# KAKUTE_mini.net
KiCad netlist of a schematic drawn in EasyEDA Pro
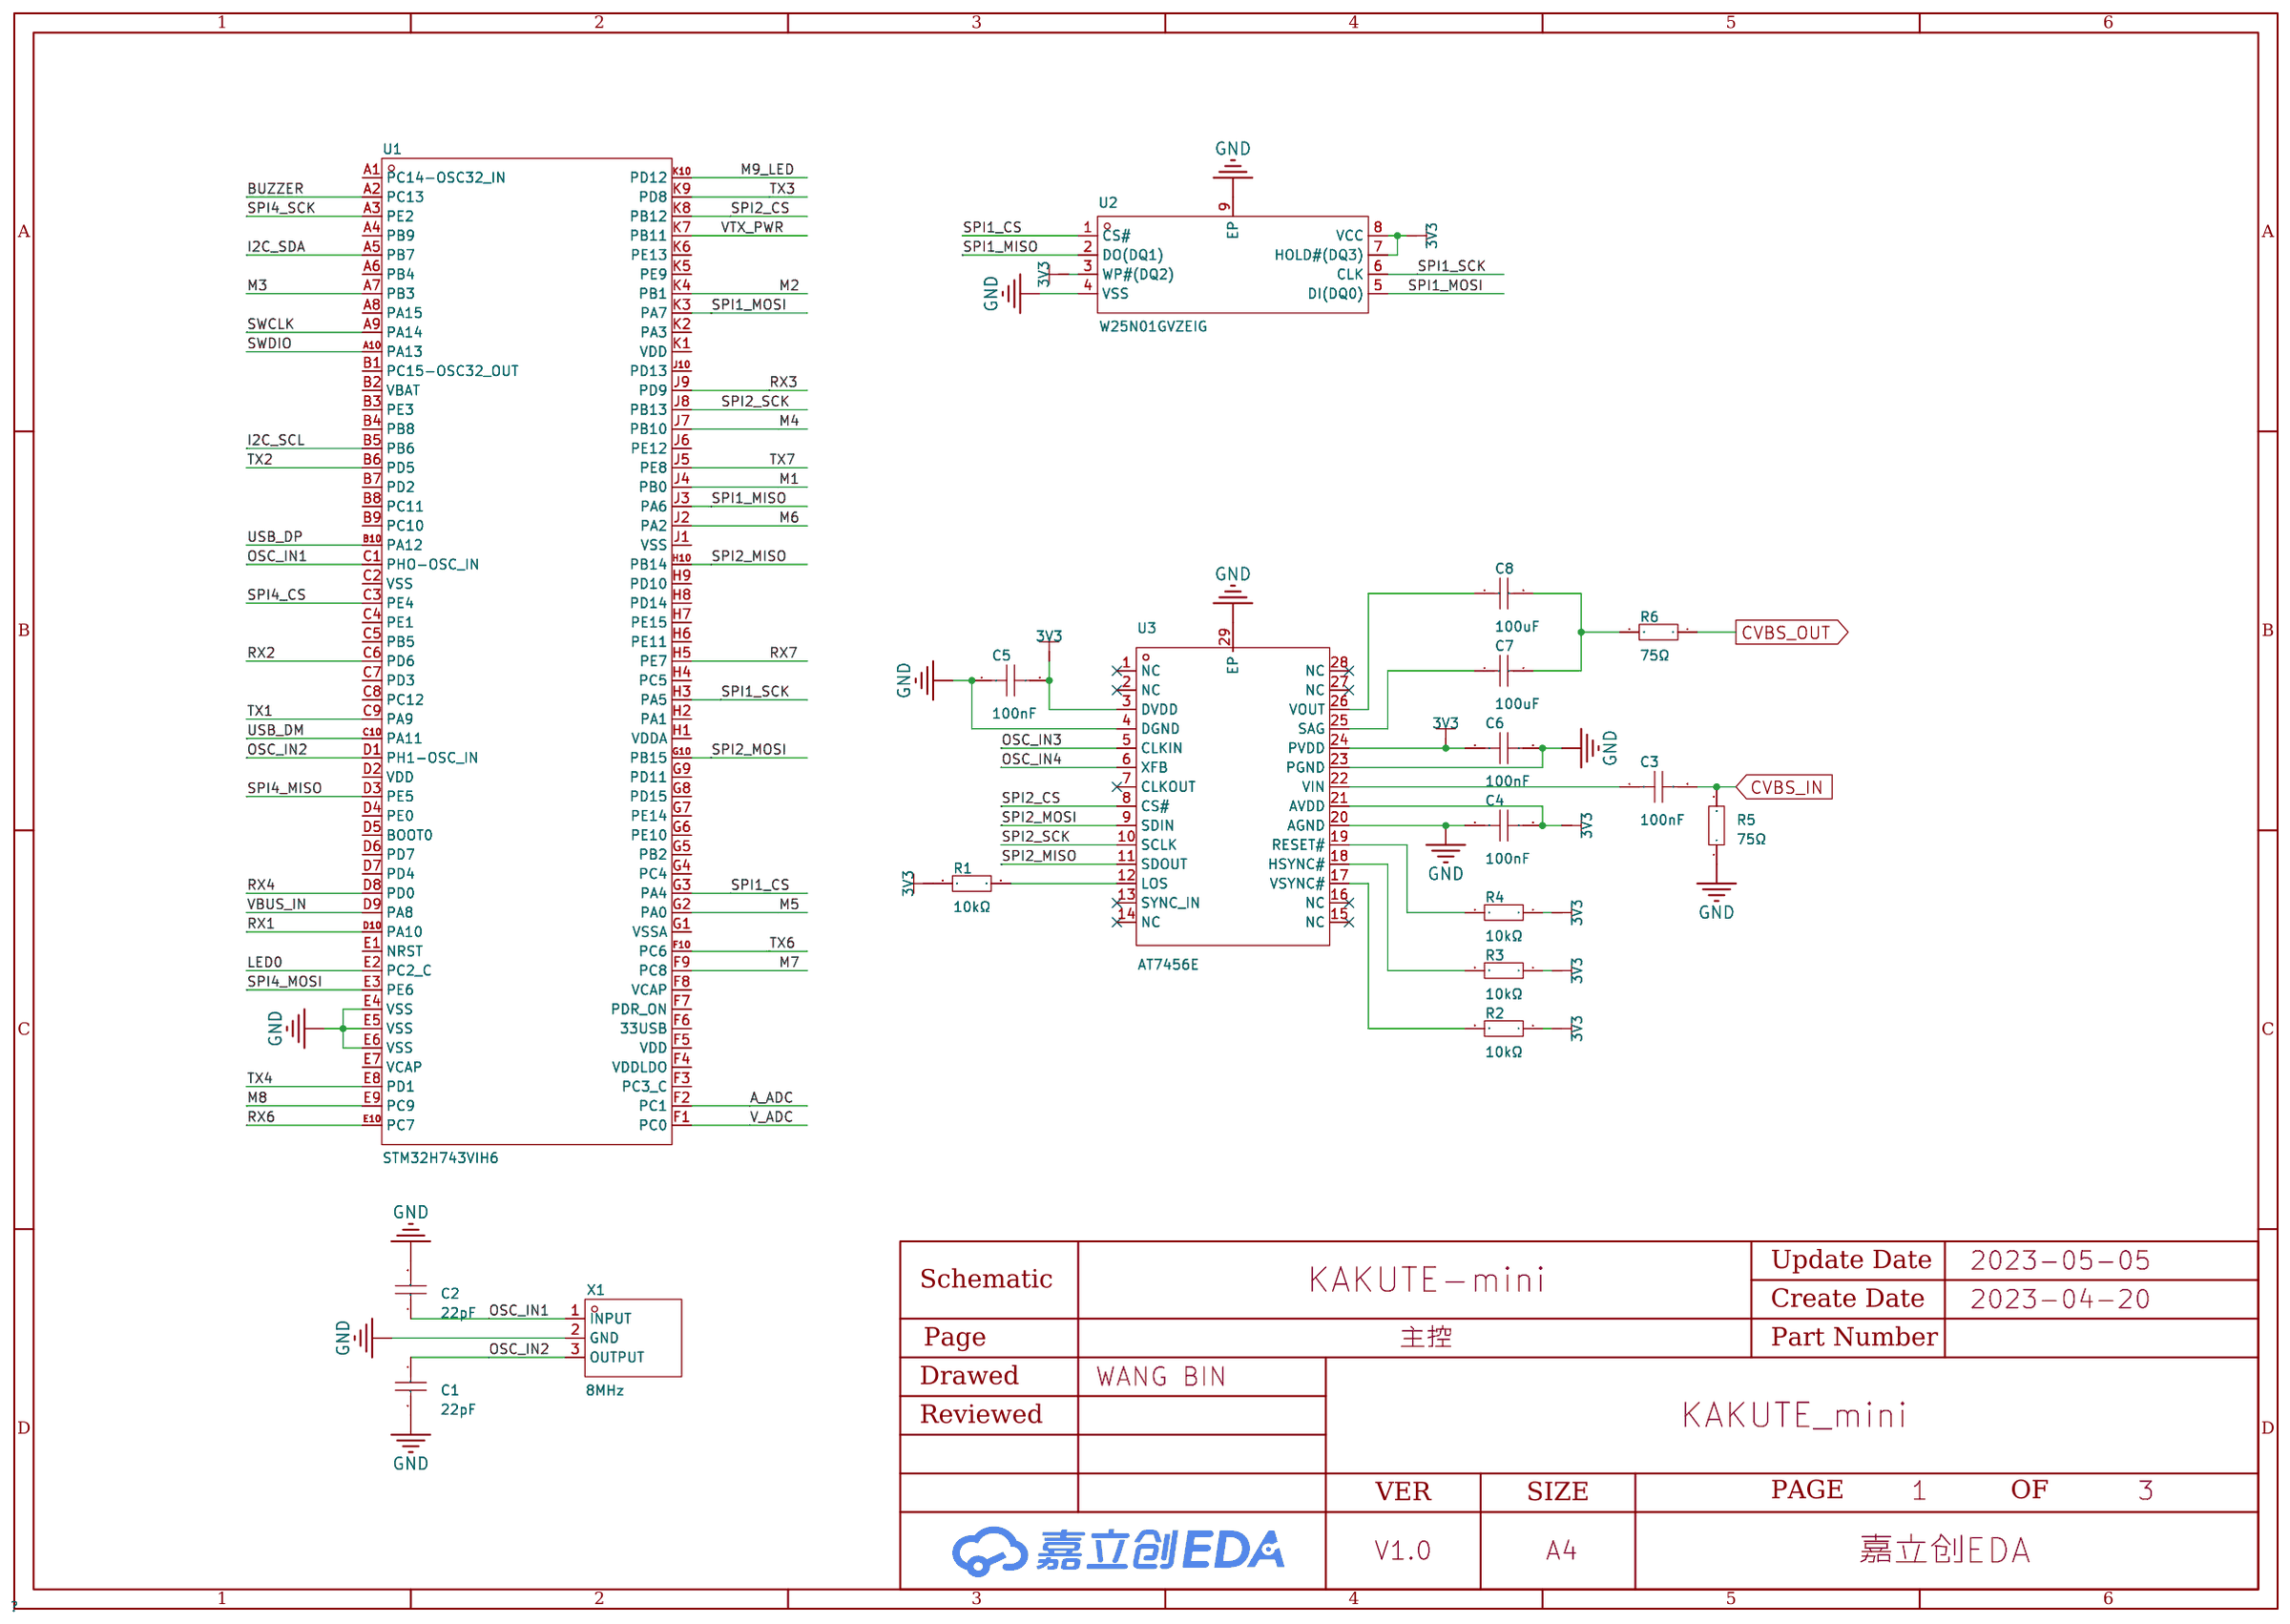
[diagram p0: 主控]
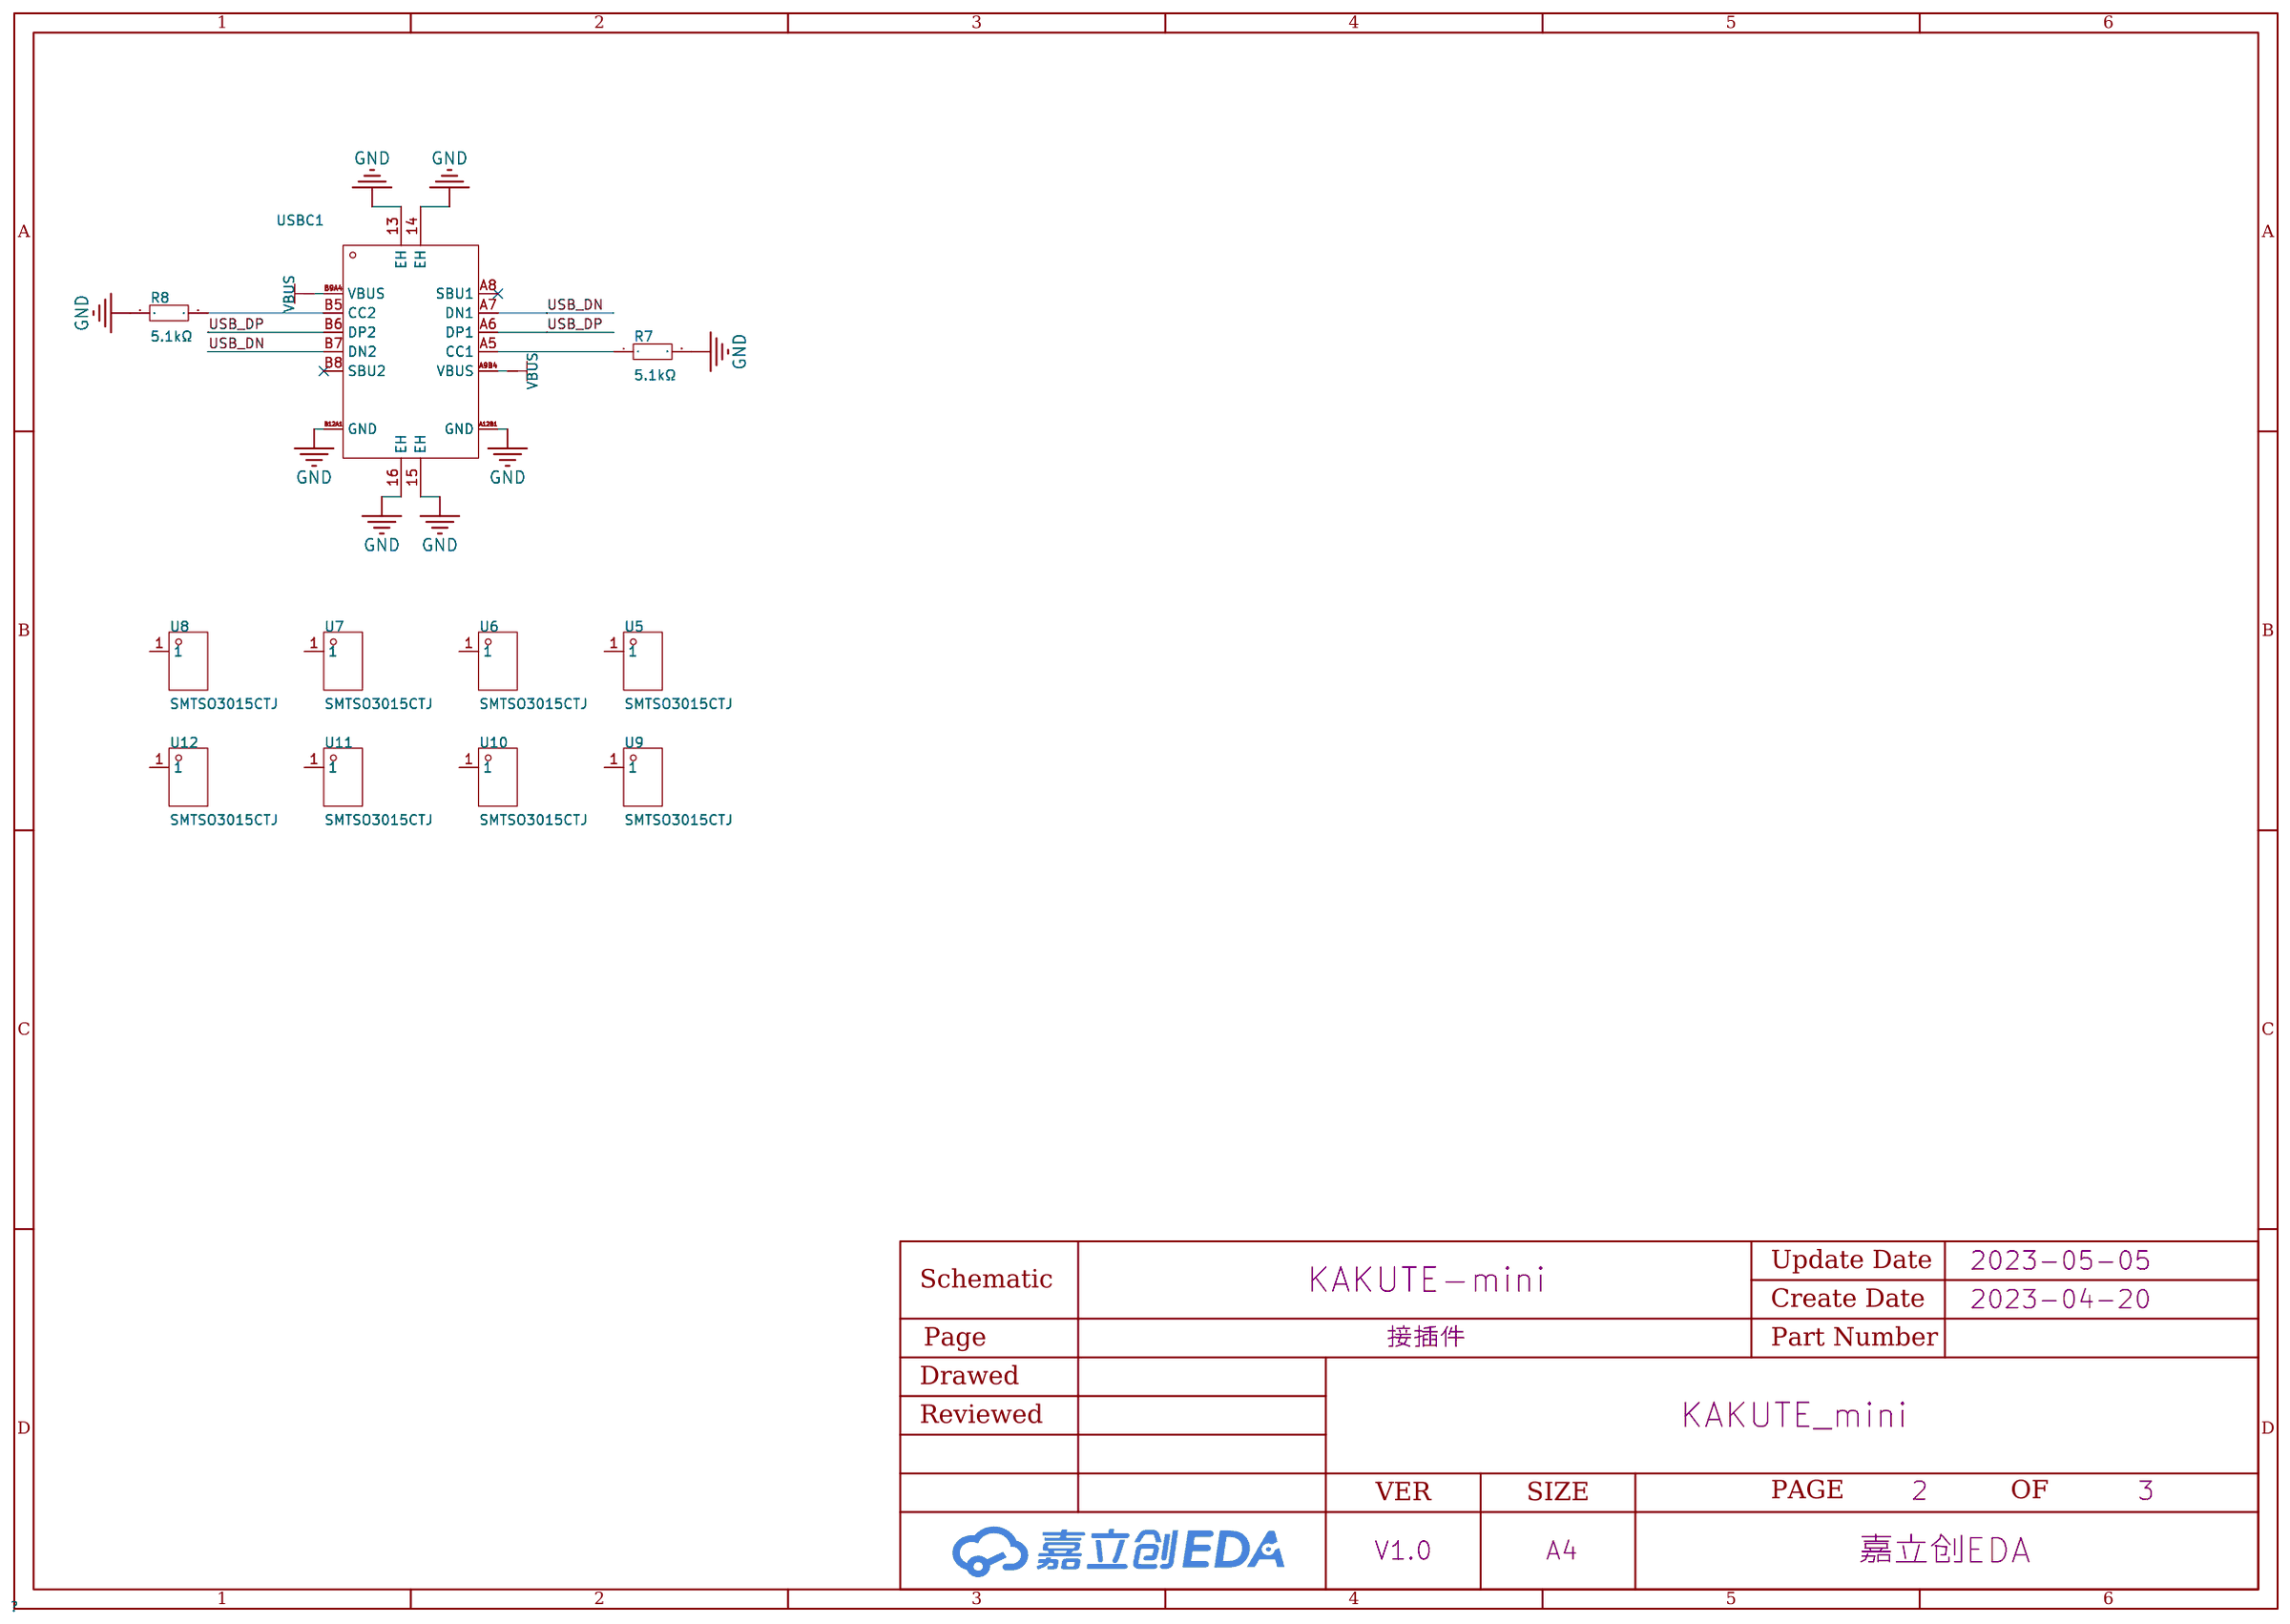
[diagram p1: 接插件]
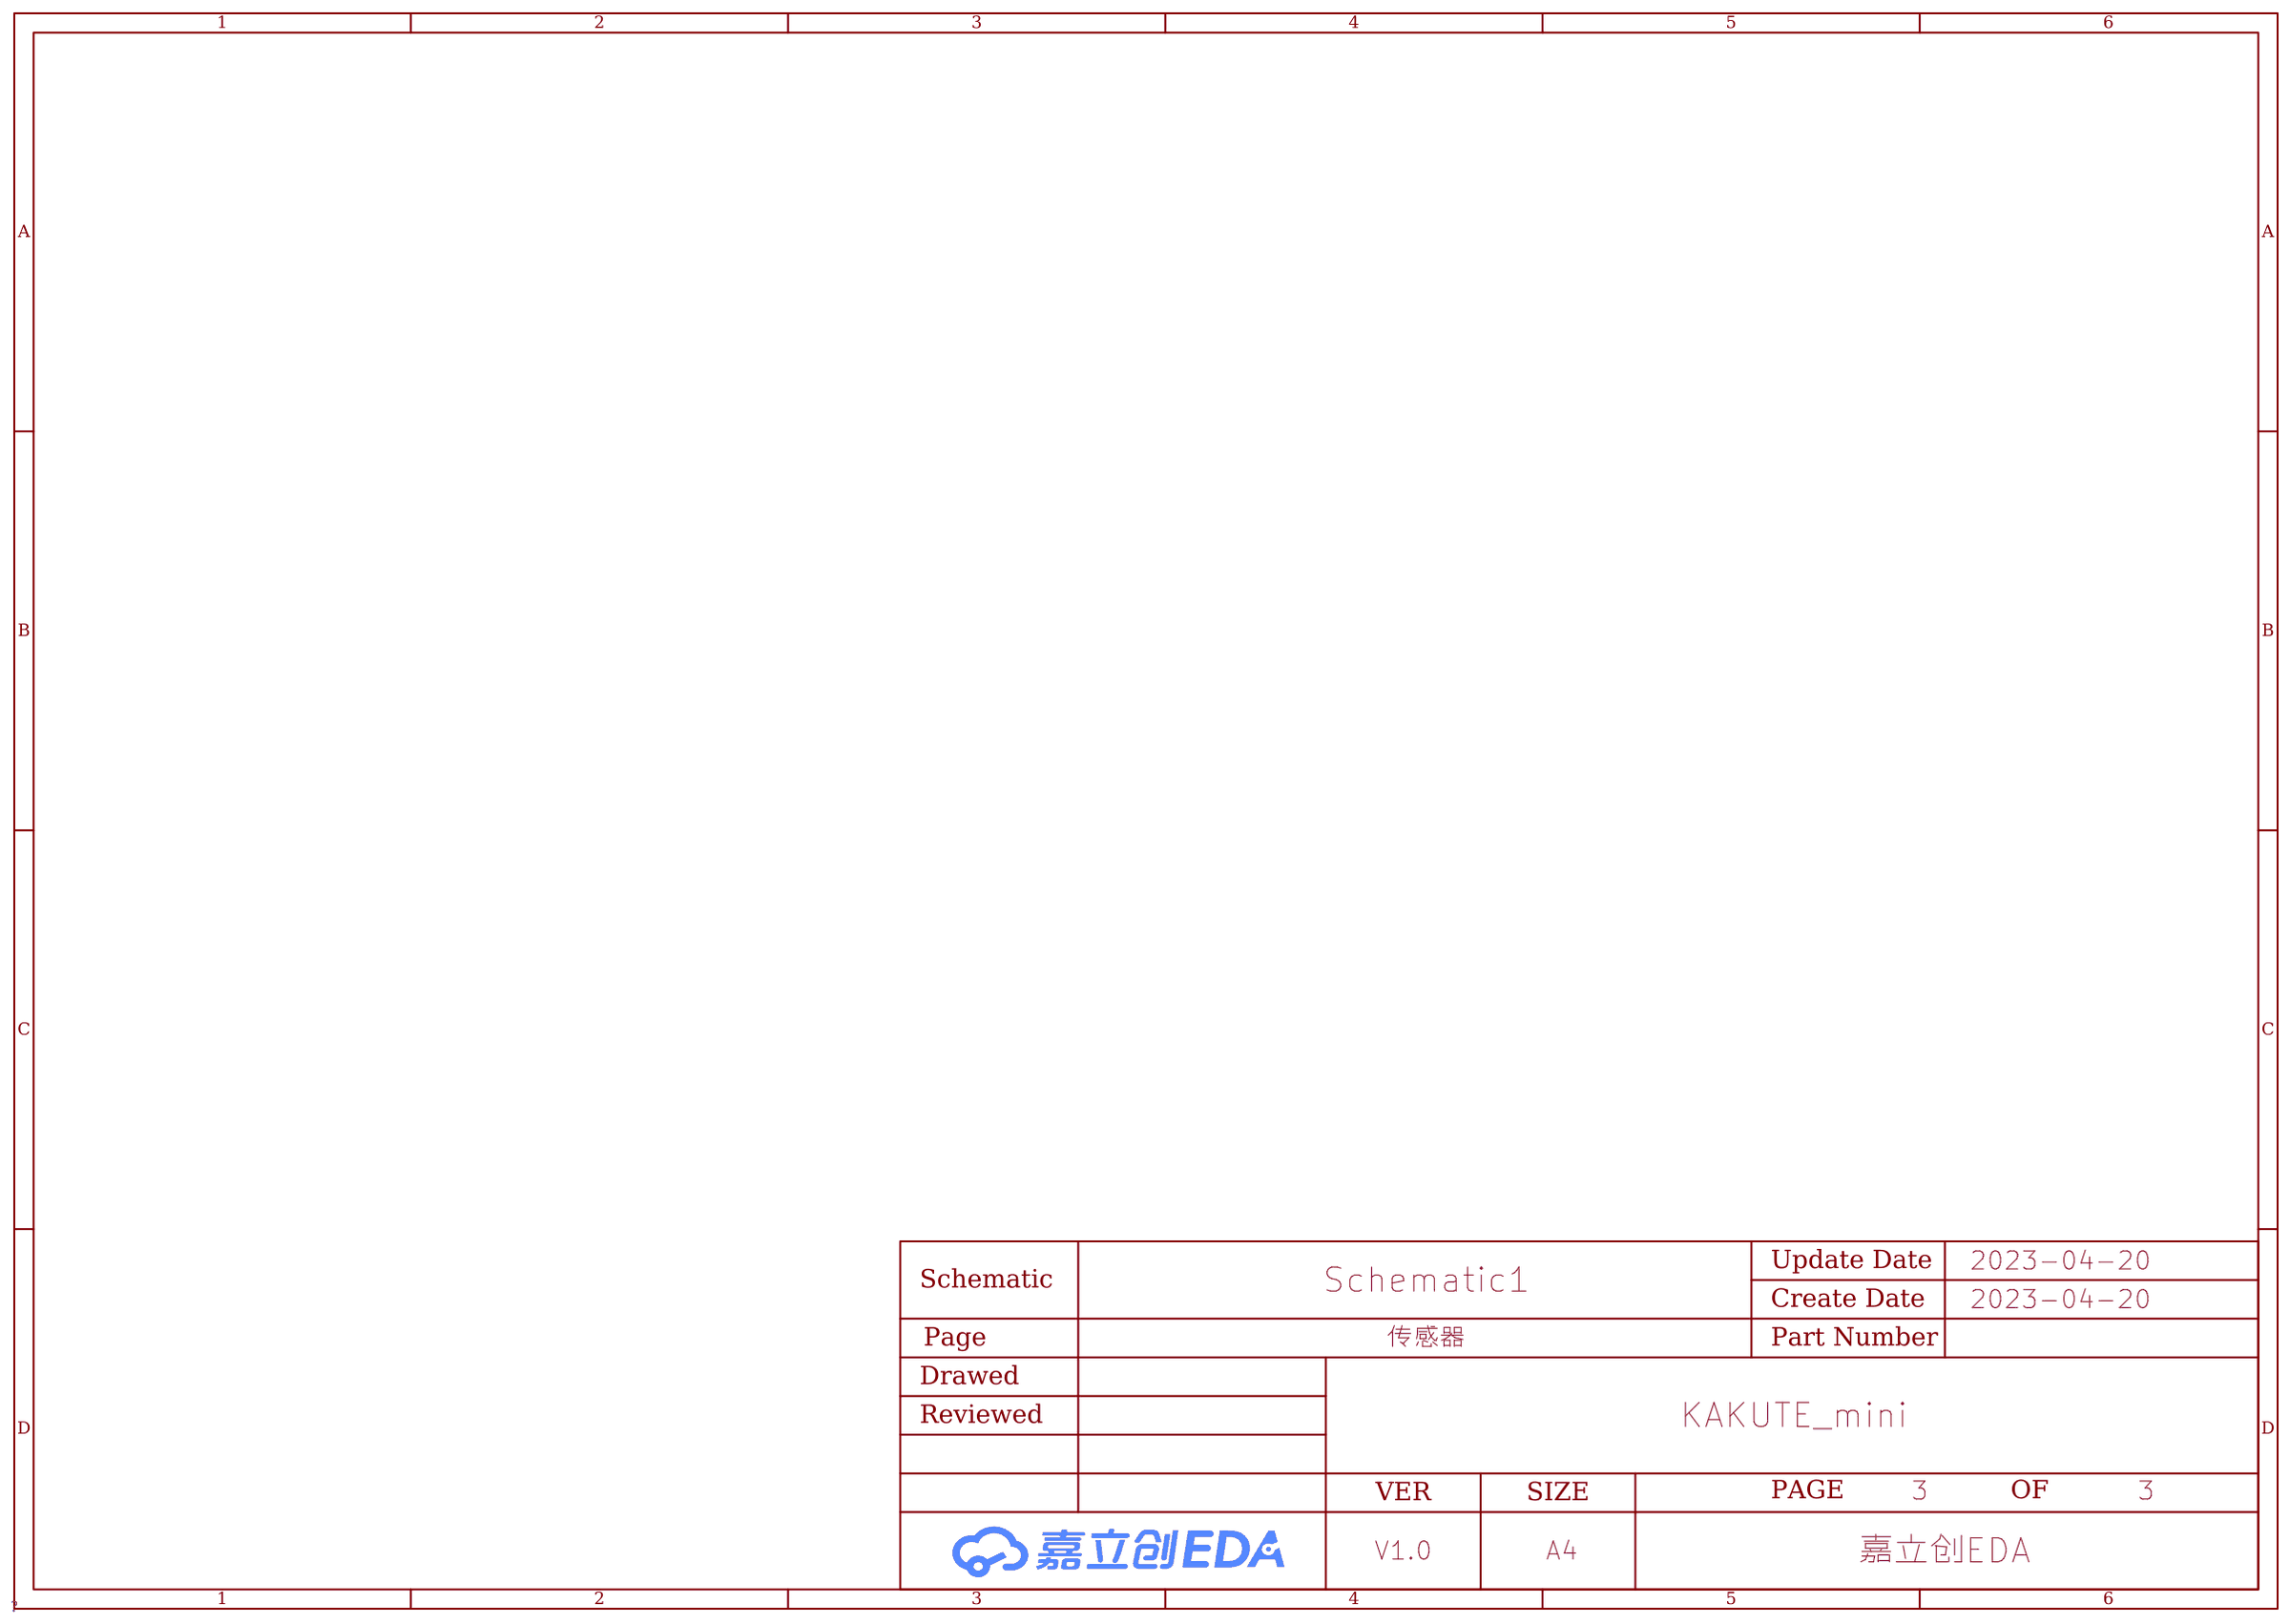
[diagram p2: 传感器]

(export (version "E")
  (design (tool "Eeschema 10.0.6"))
  (components
    (comp (ref "C1")
      (value "22pF")
      (footprint "easyedapro:C0402")
      (description "容值:22pF;精度:±5%;额定电压:50V;材质(温度系数):C0G;")
      (fields (field (name "Manufacturer Part") "0402CG220J500NT") (field (name "Manufacturer") "FH(风华)"))
      (libsource (lib "easyedapro") (part "0402CG220J500NT"))
    )
    (comp (ref "C2")
      (value "22pF")
      (footprint "easyedapro:C0402")
      (description "容值:22pF;精度:±5%;额定电压:50V;材质(温度系数):C0G;")
      (fields (field (name "Manufacturer Part") "0402CG220J500NT") (field (name "Manufacturer") "FH(风华)"))
      (libsource (lib "easyedapro") (part "0402CG220J500NT"))
    )
    (comp (ref "C3")
      (value "100nF")
      (footprint "easyedapro:C0402")
      (description "容值:100nF;精度:±10%;额定电压:50V;材质(温度系数):X7R;")
      (fields
        (field (name "Manufacturer Part") "CL05B104KB54PNC")
        (field (name "Manufacturer") "SAMSUNG(三星)")
      )
      (libsource (lib "easyedapro") (part "CL05B104KB54PNC"))
    )
    (comp (ref "C4")
      (value "100nF")
      (footprint "easyedapro:C0402")
      (description "容值:100nF;精度:±10%;额定电压:50V;材质(温度系数):X7R;")
      (fields
        (field (name "Manufacturer Part") "CL05B104KB54PNC")
        (field (name "Manufacturer") "SAMSUNG(三星)")
      )
      (libsource (lib "easyedapro") (part "CL05B104KB54PNC"))
    )
    (comp (ref "C5")
      (value "100nF")
      (footprint "easyedapro:C0402")
      (description "容值:100nF;精度:±10%;额定电压:50V;材质(温度系数):X7R;")
      (fields
        (field (name "Manufacturer Part") "CL05B104KB54PNC")
        (field (name "Manufacturer") "SAMSUNG(三星)")
      )
      (libsource (lib "easyedapro") (part "CL05B104KB54PNC"))
    )
    (comp (ref "C6")
      (value "100nF")
      (footprint "easyedapro:C0402")
      (description "容值:100nF;精度:±10%;额定电压:50V;材质(温度系数):X7R;")
      (fields
        (field (name "Manufacturer Part") "CL05B104KB54PNC")
        (field (name "Manufacturer") "SAMSUNG(三星)")
      )
      (libsource (lib "easyedapro") (part "CL05B104KB54PNC"))
    )
    (comp (ref "C7")
      (value "100uF")
      (footprint "easyedapro:C0805")
      (description "容值:100uF;精度:±20%;额定电压:6.3V;材质(温度系数):X5R;")
      (fields
        (field (name "Manufacturer Part") "GRM21BR60J107ME15L")
        (field (name "Manufacturer") "muRata(村田)")
      )
      (libsource (lib "easyedapro") (part "GRM21BR60J107ME15L"))
    )
    (comp (ref "C8")
      (value "100uF")
      (footprint "easyedapro:C0805")
      (description "容值:100uF;精度:±20%;额定电压:6.3V;材质(温度系数):X5R;")
      (fields
        (field (name "Manufacturer Part") "GRM21BR60J107ME15L")
        (field (name "Manufacturer") "muRata(村田)")
      )
      (libsource (lib "easyedapro") (part "GRM21BR60J107ME15L"))
    )
    (comp (ref "R1")
      (value "10kΩ")
      (footprint "easyedapro:R0402")
      (description "电阻类型:厚膜电阻;阻值:10kΩ;精度:±1%;功率:62.5mW;")
      (fields
        (field (name "Manufacturer Part") "0402WGF1002TCE")
        (field (name "Manufacturer") "UNI-ROYAL(厚声)")
      )
      (libsource (lib "easyedapro") (part "0402WGF1002TCE"))
    )
    (comp (ref "R2")
      (value "10kΩ")
      (footprint "easyedapro:R0402")
      (description "电阻类型:厚膜电阻;阻值:10kΩ;精度:±1%;功率:62.5mW;")
      (fields
        (field (name "Manufacturer Part") "0402WGF1002TCE")
        (field (name "Manufacturer") "UNI-ROYAL(厚声)")
      )
      (libsource (lib "easyedapro") (part "0402WGF1002TCE"))
    )
    (comp (ref "R3")
      (value "10kΩ")
      (footprint "easyedapro:R0402")
      (description "电阻类型:厚膜电阻;阻值:10kΩ;精度:±1%;功率:62.5mW;")
      (fields
        (field (name "Manufacturer Part") "0402WGF1002TCE")
        (field (name "Manufacturer") "UNI-ROYAL(厚声)")
      )
      (libsource (lib "easyedapro") (part "0402WGF1002TCE"))
    )
    (comp (ref "R4")
      (value "10kΩ")
      (footprint "easyedapro:R0402")
      (description "电阻类型:厚膜电阻;阻值:10kΩ;精度:±1%;功率:62.5mW;")
      (fields
        (field (name "Manufacturer Part") "0402WGF1002TCE")
        (field (name "Manufacturer") "UNI-ROYAL(厚声)")
      )
      (libsource (lib "easyedapro") (part "0402WGF1002TCE"))
    )
    (comp (ref "R5")
      (value "75Ω")
      (footprint "easyedapro:R0402")
      (description "电阻类型:厚膜电阻;阻值:75Ω;精度:±1%;功率:62.5mW;")
      (fields
        (field (name "Manufacturer Part") "0402WGF750JTCE")
        (field (name "Manufacturer") "UNI-ROYAL(厚声)")
      )
      (libsource (lib "easyedapro") (part "0402WGF750JTCE"))
    )
    (comp (ref "R6")
      (value "75Ω")
      (footprint "easyedapro:R0402")
      (description "电阻类型:厚膜电阻;阻值:75Ω;精度:±1%;功率:62.5mW;")
      (fields
        (field (name "Manufacturer Part") "0402WGF750JTCE")
        (field (name "Manufacturer") "UNI-ROYAL(厚声)")
      )
      (libsource (lib "easyedapro") (part "0402WGF750JTCE"))
    )
    (comp (ref "U1")
      (value "STM32H743VIH6")
      (footprint "easyedapro:BGA-100_L8.0-W8.0-P0.80-R10-C10-BL")
      (description "32位Arm Cortex -M7 480MHz mcu,高达2MB的Flash,高达1MB的RAM,46com和模拟接口")
      (fields (field (name "Manufacturer") "ST(意法半导体)"))
      (libsource (lib "easyedapro") (part "STM32H743VIH6"))
    )
    (comp (ref "U2")
      (value "W25N01GVZEIG")
      (footprint "easyedapro:WSON-8_L8.0-W6.10-P1.27-BL-EP")
      (description "存储器类型:-;存储器构架(格式):-;技术:-;存储器容量:-;时钟频率:-;存储器接口类型:-;")
      (fields (field (name "Manufacturer") "WINBOND(华邦)"))
      (libsource (lib "easyedapro") (part "W25N01GVZEIG_C907680"))
    )
    (comp (ref "U3")
      (value "AT7456E")
      (footprint "easyedapro:TSSOP-28_L9.7-W4.4-P0.65-LS6.4-BL-EP-2")
      (description "视频字符叠加芯片，跟MAX7456-pin-pin")
      (fields (field (name "Manufacturer") "杭州中科微"))
      (libsource (lib "easyedapro") (part "AT7456E"))
    )
    (comp (ref "X1")
      (value "8MHz")
      (footprint "easyedapro:OSC-SMD_3P-L3.2-W1.3-P1.20-L")
      (description "频率:8MHz;频率公差:±0.07%;频率稳定度:-;")
      (fields
        (field (name "Manufacturer Part") "CSTNE8M00GH5L000R0")
        (field (name "Manufacturer") "muRata(村田)")
      )
      (libsource (lib "easyedapro") (part "CSTNE8M00GH5L000R0"))
    )
    (comp (ref "R7")
      (value "5.1kΩ")
      (footprint "easyedapro:R0402")
      (description "电阻类型:厚膜电阻;阻值:5.1kΩ;精度:±1%;功率:62.5mW;")
      (fields
        (field (name "Manufacturer Part") "0402WGF5101TCE")
        (field (name "Manufacturer") "UNI-ROYAL(厚声)")
      )
      (libsource (lib "easyedapro") (part "0402WGF5101TCE"))
    )
    (comp (ref "R8")
      (value "5.1kΩ")
      (footprint "easyedapro:R0402")
      (description "电阻类型:厚膜电阻;阻值:5.1kΩ;精度:±1%;功率:62.5mW;")
      (fields
        (field (name "Manufacturer Part") "0402WGF5101TCE")
        (field (name "Manufacturer") "UNI-ROYAL(厚声)")
      )
      (libsource (lib "easyedapro") (part "0402WGF5101TCE"))
    )
    (comp (ref "U5")
      (value "SMTSO3015CTJ")
      (footprint "easyedapro:SMD_BD5.6-L5.6-W5.6-D4.1")
      (description "M3x5.56xL1.5+1.53")
      (fields (field (name "Manufacturer") "Sinhoo(雄和远景)"))
      (libsource (lib "easyedapro") (part "SMTSO3015CTJ"))
    )
    (comp (ref "U6")
      (value "SMTSO3015CTJ")
      (footprint "easyedapro:SMD_BD5.6-L5.6-W5.6-D4.1")
      (description "M3x5.56xL1.5+1.53")
      (fields (field (name "Manufacturer") "Sinhoo(雄和远景)"))
      (libsource (lib "easyedapro") (part "SMTSO3015CTJ"))
    )
    (comp (ref "U7")
      (value "SMTSO3015CTJ")
      (footprint "easyedapro:SMD_BD5.6-L5.6-W5.6-D4.1")
      (description "M3x5.56xL1.5+1.53")
      (fields (field (name "Manufacturer") "Sinhoo(雄和远景)"))
      (libsource (lib "easyedapro") (part "SMTSO3015CTJ"))
    )
    (comp (ref "U8")
      (value "SMTSO3015CTJ")
      (footprint "easyedapro:SMD_BD5.6-L5.6-W5.6-D4.1")
      (description "M3x5.56xL1.5+1.53")
      (fields (field (name "Manufacturer") "Sinhoo(雄和远景)"))
      (libsource (lib "easyedapro") (part "SMTSO3015CTJ"))
    )
    (comp (ref "U9")
      (value "SMTSO3015CTJ")
      (footprint "easyedapro:SMD_BD5.6-L5.6-W5.6-D4.1")
      (description "M3x5.56xL1.5+1.53")
      (fields (field (name "Manufacturer") "Sinhoo(雄和远景)"))
      (libsource (lib "easyedapro") (part "SMTSO3015CTJ"))
    )
    (comp (ref "U10")
      (value "SMTSO3015CTJ")
      (footprint "easyedapro:SMD_BD5.6-L5.6-W5.6-D4.1")
      (description "M3x5.56xL1.5+1.53")
      (fields (field (name "Manufacturer") "Sinhoo(雄和远景)"))
      (libsource (lib "easyedapro") (part "SMTSO3015CTJ"))
    )
    (comp (ref "U11")
      (value "SMTSO3015CTJ")
      (footprint "easyedapro:SMD_BD5.6-L5.6-W5.6-D4.1")
      (description "M3x5.56xL1.5+1.53")
      (fields (field (name "Manufacturer") "Sinhoo(雄和远景)"))
      (libsource (lib "easyedapro") (part "SMTSO3015CTJ"))
    )
    (comp (ref "U12")
      (value "SMTSO3015CTJ")
      (footprint "easyedapro:SMD_BD5.6-L5.6-W5.6-D4.1")
      (description "M3x5.56xL1.5+1.53")
      (fields (field (name "Manufacturer") "Sinhoo(雄和远景)"))
      (libsource (lib "easyedapro") (part "SMTSO3015CTJ"))
    )
    (comp (ref "USBC1")
      (value "918-418K2024S40000")
      (footprint "easyedapro:USB-C-SMD_TYPE-C-USB-4")
      (description "连接器类型:Type-C;标准:-;公母:母座;触点数量:16;端口数量:1;")
      (fields (field (name "Manufacturer") "精拓金"))
      (libsource (lib "easyedapro") (part "TYPE-C 3.1 MT 16P_C168688"))
    )
  )
  (nets
    (net (code "1") (name "3V3") (class "Default")
      (node (ref "C4") (pin "2") (pinfunction "2_2") (pintype "input"))
      (node (ref "C5") (pin "2") (pinfunction "2_2") (pintype "input"))
      (node (ref "C6") (pin "1") (pinfunction "1_1") (pintype "input"))
      (node (ref "R1") (pin "1") (pinfunction "1_1") (pintype "input"))
      (node (ref "R2") (pin "1") (pinfunction "1_1") (pintype "input"))
      (node (ref "R3") (pin "1") (pinfunction "1_1") (pintype "input"))
      (node (ref "R4") (pin "1") (pinfunction "1_1") (pintype "input"))
      (node (ref "U2") (pin "3") (pinfunction "WP#(DQ2)_3") (pintype "input"))
      (node (ref "U2") (pin "7") (pinfunction "HOLD#(DQ3)_7") (pintype "input"))
      (node (ref "U2") (pin "8") (pinfunction "VCC_8") (pintype "input"))
      (node (ref "U3") (pin "21") (pinfunction "AVDD_21") (pintype "input"))
      (node (ref "U3") (pin "24") (pinfunction "PVDD_24") (pintype "input"))
      (node (ref "U3") (pin "3") (pinfunction "DVDD_3") (pintype "input"))
    )
    (net (code "2") (name "A_ADC") (class "Default")
      (node (ref "U1") (pin "F2") (pinfunction "PC1_F2") (pintype "input"))
    )
    (net (code "3") (name "BUZZER") (class "Default")
      (node (ref "U1") (pin "A2") (pinfunction "PC13_A2") (pintype "input"))
    )
    (net (code "4") (name "CVBS_IN") (class "Default")
      (node (ref "C3") (pin "2") (pinfunction "2_2") (pintype "input"))
      (node (ref "R5") (pin "2") (pinfunction "2_2") (pintype "input"))
    )
    (net (code "5") (name "CVBS_OUT") (class "Default")
      (node (ref "R6") (pin "1") (pinfunction "1_1") (pintype "input"))
    )
    (net (code "6") (name "GND") (class "Default")
      (node (ref "C1") (pin "2") (pinfunction "2_2") (pintype "input"))
      (node (ref "C2") (pin "2") (pinfunction "2_2") (pintype "input"))
      (node (ref "C4") (pin "1") (pinfunction "1_1") (pintype "input"))
      (node (ref "C5") (pin "1") (pinfunction "1_1") (pintype "input"))
      (node (ref "C6") (pin "2") (pinfunction "2_2") (pintype "input"))
      (node (ref "R5") (pin "1") (pinfunction "1_1") (pintype "input"))
      (node (ref "R7") (pin "2") (pinfunction "2_2") (pintype "input"))
      (node (ref "R8") (pin "1") (pinfunction "1_1") (pintype "input"))
      (node (ref "U1") (pin "E4") (pinfunction "VSS_E4") (pintype "input"))
      (node (ref "U1") (pin "E5") (pinfunction "VSS_E5") (pintype "input"))
      (node (ref "U1") (pin "E6") (pinfunction "VSS_E6") (pintype "input"))
      (node (ref "U2") (pin "4") (pinfunction "VSS_4") (pintype "input"))
      (node (ref "U2") (pin "9") (pinfunction "EP_9") (pintype "input"))
      (node (ref "U3") (pin "20") (pinfunction "AGND_20") (pintype "input"))
      (node (ref "U3") (pin "23") (pinfunction "PGND_23") (pintype "input"))
      (node (ref "U3") (pin "29") (pinfunction "EP_29") (pintype "input"))
      (node (ref "U3") (pin "4") (pinfunction "DGND_4") (pintype "input"))
      (node (ref "USBC1") (pin "13") (pinfunction "EH_13") (pintype "input"))
      (node (ref "USBC1") (pin "14") (pinfunction "EH_14") (pintype "input"))
      (node (ref "USBC1") (pin "15") (pinfunction "EH_15") (pintype "input"))
      (node (ref "USBC1") (pin "16") (pinfunction "EH_16") (pintype "input"))
      (node (ref "USBC1") (pin "A12B1") (pinfunction "GND_A12B1") (pintype "input"))
      (node (ref "USBC1") (pin "B12A1") (pinfunction "GND_B12A1") (pintype "input"))
      (node (ref "X1") (pin "2") (pinfunction "GND_2") (pintype "input"))
    )
    (net (code "7") (name "I2C_SCL") (class "Default")
      (node (ref "U1") (pin "B5") (pinfunction "PB6_B5") (pintype "input"))
    )
    (net (code "8") (name "I2C_SDA") (class "Default")
      (node (ref "U1") (pin "A5") (pinfunction "PB7_A5") (pintype "input"))
    )
    (net (code "9") (name "LED0") (class "Default")
      (node (ref "U1") (pin "E2") (pinfunction "PC2_C_E2") (pintype "input"))
    )
    (net (code "10") (name "M1") (class "Default")
      (node (ref "U1") (pin "J4") (pinfunction "PB0_J4") (pintype "input"))
    )
    (net (code "11") (name "M2") (class "Default")
      (node (ref "U1") (pin "K4") (pinfunction "PB1_K4") (pintype "input"))
    )
    (net (code "12") (name "M3") (class "Default")
      (node (ref "U1") (pin "A7") (pinfunction "PB3_A7") (pintype "input"))
    )
    (net (code "13") (name "M4") (class "Default")
      (node (ref "U1") (pin "J7") (pinfunction "PB10_J7") (pintype "input"))
    )
    (net (code "14") (name "M5") (class "Default")
      (node (ref "U1") (pin "G2") (pinfunction "PA0_G2") (pintype "input"))
    )
    (net (code "15") (name "M6") (class "Default")
      (node (ref "U1") (pin "J2") (pinfunction "PA2_J2") (pintype "input"))
    )
    (net (code "16") (name "M7") (class "Default")
      (node (ref "U1") (pin "F9") (pinfunction "PC8_F9") (pintype "input"))
    )
    (net (code "17") (name "M8") (class "Default")
      (node (ref "U1") (pin "E9") (pinfunction "PC9_E9") (pintype "input"))
    )
    (net (code "18") (name "M9_LED") (class "Default")
      (node (ref "U1") (pin "K10") (pinfunction "PD12_K10") (pintype "input"))
    )
    (net (code "19") (name "Net-(C7-Pad2)") (class "Default")
      (node (ref "C7") (pin "2") (pinfunction "2_2") (pintype "input"))
      (node (ref "C8") (pin "2") (pinfunction "2_2") (pintype "input"))
      (node (ref "R6") (pin "2") (pinfunction "2_2") (pintype "input"))
    )
    (net (code "20") (name "Net-(U3-HSYNC#)") (class "Default")
      (node (ref "R3") (pin "2") (pinfunction "2_2") (pintype "input"))
      (node (ref "U3") (pin "18") (pinfunction "HSYNC#_18") (pintype "input"))
    )
    (net (code "21") (name "Net-(U3-LOS)") (class "Default")
      (node (ref "R1") (pin "2") (pinfunction "2_2") (pintype "input"))
      (node (ref "U3") (pin "12") (pinfunction "LOS_12") (pintype "input"))
    )
    (net (code "22") (name "Net-(U3-RESET#)") (class "Default")
      (node (ref "R4") (pin "2") (pinfunction "2_2") (pintype "input"))
      (node (ref "U3") (pin "19") (pinfunction "RESET#_19") (pintype "input"))
    )
    (net (code "23") (name "Net-(U3-SAG)") (class "Default")
      (node (ref "C7") (pin "1") (pinfunction "1_1") (pintype "input"))
      (node (ref "U3") (pin "25") (pinfunction "SAG_25") (pintype "input"))
    )
    (net (code "24") (name "Net-(U3-VIN)") (class "Default")
      (node (ref "C3") (pin "1") (pinfunction "1_1") (pintype "input"))
      (node (ref "U3") (pin "22") (pinfunction "VIN_22") (pintype "input"))
    )
    (net (code "25") (name "Net-(U3-VOUT)") (class "Default")
      (node (ref "C8") (pin "1") (pinfunction "1_1") (pintype "input"))
      (node (ref "U3") (pin "26") (pinfunction "VOUT_26") (pintype "input"))
    )
    (net (code "26") (name "Net-(U3-VSYNC#)") (class "Default")
      (node (ref "R2") (pin "2") (pinfunction "2_2") (pintype "input"))
      (node (ref "U3") (pin "17") (pinfunction "VSYNC#_17") (pintype "input"))
    )
    (net (code "27") (name "Net-(USBC1-CC1)") (class "Default")
      (node (ref "R7") (pin "1") (pinfunction "1_1") (pintype "input"))
      (node (ref "USBC1") (pin "A5") (pinfunction "CC1_A5") (pintype "input"))
    )
    (net (code "28") (name "Net-(USBC1-CC2)") (class "Default")
      (node (ref "R8") (pin "2") (pinfunction "2_2") (pintype "input"))
      (node (ref "USBC1") (pin "B5") (pinfunction "CC2_B5") (pintype "input"))
    )
    (net (code "29") (name "OSC_IN1") (class "Default")
      (node (ref "C2") (pin "1") (pinfunction "1_1") (pintype "input"))
      (node (ref "U1") (pin "C1") (pinfunction "PHO-OSC_IN_C1") (pintype "input"))
      (node (ref "X1") (pin "1") (pinfunction "INPUT_1") (pintype "input"))
    )
    (net (code "30") (name "OSC_IN2") (class "Default")
      (node (ref "C1") (pin "1") (pinfunction "1_1") (pintype "input"))
      (node (ref "U1") (pin "D1") (pinfunction "PH1-OSC_IN_D1") (pintype "input"))
      (node (ref "X1") (pin "3") (pinfunction "OUTPUT_3") (pintype "input"))
    )
    (net (code "31") (name "OSC_IN3") (class "Default")
      (node (ref "U3") (pin "5") (pinfunction "CLKIN_5") (pintype "input"))
    )
    (net (code "32") (name "OSC_IN4") (class "Default")
      (node (ref "U3") (pin "6") (pinfunction "XFB_6") (pintype "input"))
    )
    (net (code "33") (name "RX1") (class "Default")
      (node (ref "U1") (pin "D10") (pinfunction "PA10_D10") (pintype "input"))
    )
    (net (code "34") (name "RX2") (class "Default")
      (node (ref "U1") (pin "C6") (pinfunction "PD6_C6") (pintype "input"))
    )
    (net (code "35") (name "RX3") (class "Default")
      (node (ref "U1") (pin "J9") (pinfunction "PD9_J9") (pintype "input"))
    )
    (net (code "36") (name "RX4") (class "Default")
      (node (ref "U1") (pin "D8") (pinfunction "PD0_D8") (pintype "input"))
    )
    (net (code "37") (name "RX6") (class "Default")
      (node (ref "U1") (pin "E10") (pinfunction "PC7_E10") (pintype "input"))
    )
    (net (code "38") (name "RX7") (class "Default")
      (node (ref "U1") (pin "H5") (pinfunction "PE7_H5") (pintype "input"))
    )
    (net (code "39") (name "SPI1_CS") (class "Default")
      (node (ref "U1") (pin "G3") (pinfunction "PA4_G3") (pintype "input"))
      (node (ref "U2") (pin "1") (pinfunction "CS#_1") (pintype "input"))
    )
    (net (code "40") (name "SPI1_MISO") (class "Default")
      (node (ref "U1") (pin "J3") (pinfunction "PA6_J3") (pintype "input"))
      (node (ref "U2") (pin "2") (pinfunction "DO(DQ1)_2") (pintype "input"))
    )
    (net (code "41") (name "SPI1_MOSI") (class "Default")
      (node (ref "U1") (pin "K3") (pinfunction "PA7_K3") (pintype "input"))
      (node (ref "U2") (pin "5") (pinfunction "DI(DQ0)_5") (pintype "input"))
    )
    (net (code "42") (name "SPI1_SCK") (class "Default")
      (node (ref "U1") (pin "H3") (pinfunction "PA5_H3") (pintype "input"))
      (node (ref "U2") (pin "6") (pinfunction "CLK_6") (pintype "input"))
    )
    (net (code "43") (name "SPI2_CS") (class "Default")
      (node (ref "U1") (pin "K8") (pinfunction "PB12_K8") (pintype "input"))
      (node (ref "U3") (pin "8") (pinfunction "CS#_8") (pintype "input"))
    )
    (net (code "44") (name "SPI2_MISO") (class "Default")
      (node (ref "U1") (pin "H10") (pinfunction "PB14_H10") (pintype "input"))
      (node (ref "U3") (pin "11") (pinfunction "SDOUT_11") (pintype "input"))
    )
    (net (code "45") (name "SPI2_MOSI") (class "Default")
      (node (ref "U1") (pin "G10") (pinfunction "PB15_G10") (pintype "input"))
      (node (ref "U3") (pin "9") (pinfunction "SDIN_9") (pintype "input"))
    )
    (net (code "46") (name "SPI2_SCK") (class "Default")
      (node (ref "U1") (pin "J8") (pinfunction "PB13_J8") (pintype "input"))
      (node (ref "U3") (pin "10") (pinfunction "SCLK_10") (pintype "input"))
    )
    (net (code "47") (name "SPI4_CS") (class "Default")
      (node (ref "U1") (pin "C3") (pinfunction "PE4_C3") (pintype "input"))
    )
    (net (code "48") (name "SPI4_MISO") (class "Default")
      (node (ref "U1") (pin "D3") (pinfunction "PE5_D3") (pintype "input"))
    )
    (net (code "49") (name "SPI4_MOSI") (class "Default")
      (node (ref "U1") (pin "E3") (pinfunction "PE6_E3") (pintype "input"))
    )
    (net (code "50") (name "SPI4_SCK") (class "Default")
      (node (ref "U1") (pin "A3") (pinfunction "PE2_A3") (pintype "input"))
    )
    (net (code "51") (name "SWCLK") (class "Default")
      (node (ref "U1") (pin "A9") (pinfunction "PA14_A9") (pintype "input"))
    )
    (net (code "52") (name "SWDIO") (class "Default")
      (node (ref "U1") (pin "A10") (pinfunction "PA13_A10") (pintype "input"))
    )
    (net (code "53") (name "TX1") (class "Default")
      (node (ref "U1") (pin "C9") (pinfunction "PA9_C9") (pintype "input"))
    )
    (net (code "54") (name "TX2") (class "Default")
      (node (ref "U1") (pin "B6") (pinfunction "PD5_B6") (pintype "input"))
    )
    (net (code "55") (name "TX3") (class "Default")
      (node (ref "U1") (pin "K9") (pinfunction "PD8_K9") (pintype "input"))
    )
    (net (code "56") (name "TX4") (class "Default")
      (node (ref "U1") (pin "E8") (pinfunction "PD1_E8") (pintype "input"))
    )
    (net (code "57") (name "TX6") (class "Default")
      (node (ref "U1") (pin "F10") (pinfunction "PC6_F10") (pintype "input"))
    )
    (net (code "58") (name "TX7") (class "Default")
      (node (ref "U1") (pin "J5") (pinfunction "PE8_J5") (pintype "input"))
    )
    (net (code "59") (name "USB_DM") (class "Default")
      (node (ref "U1") (pin "C10") (pinfunction "PA11_C10") (pintype "input"))
    )
    (net (code "60") (name "USB_DN") (class "Default")
      (node (ref "USBC1") (pin "A7") (pinfunction "DN1_A7") (pintype "input"))
      (node (ref "USBC1") (pin "B7") (pinfunction "DN2_B7") (pintype "input"))
    )
    (net (code "61") (name "USB_DP") (class "Default")
      (node (ref "U1") (pin "B10") (pinfunction "PA12_B10") (pintype "input"))
      (node (ref "USBC1") (pin "A6") (pinfunction "DP1_A6") (pintype "input"))
      (node (ref "USBC1") (pin "B6") (pinfunction "DP2_B6") (pintype "input"))
    )
    (net (code "62") (name "VBUS") (class "Default")
      (node (ref "USBC1") (pin "A9B4") (pinfunction "VBUS_A9B4") (pintype "input"))
      (node (ref "USBC1") (pin "B9A4") (pinfunction "VBUS_B9A4") (pintype "input"))
    )
    (net (code "63") (name "VBUS_IN") (class "Default")
      (node (ref "U1") (pin "D9") (pinfunction "PA8_D9") (pintype "input"))
    )
    (net (code "64") (name "VTX_PWR") (class "Default")
      (node (ref "U1") (pin "K7") (pinfunction "PB11_K7") (pintype "input"))
    )
    (net (code "65") (name "V_ADC") (class "Default")
      (node (ref "U1") (pin "F1") (pinfunction "PC0_F1") (pintype "input"))
    )
    (net (code "66") (name "unconnected-(U1-33USB-PadF6)") (class "Default")
      (node (ref "U1") (pin "F6") (pinfunction "33USB_F6") (pintype "input"))
    )
    (net (code "67") (name "unconnected-(U1-BOOT0-PadD5)") (class "Default")
      (node (ref "U1") (pin "D5") (pinfunction "BOOT0_D5") (pintype "input"))
    )
    (net (code "68") (name "unconnected-(U1-NRST-PadE1)") (class "Default")
      (node (ref "U1") (pin "E1") (pinfunction "NRST_E1") (pintype "input"))
    )
    (net (code "69") (name "unconnected-(U1-PA1-PadH2)") (class "Default")
      (node (ref "U1") (pin "H2") (pinfunction "PA1_H2") (pintype "input"))
    )
    (net (code "70") (name "unconnected-(U1-PA3-PadK2)") (class "Default")
      (node (ref "U1") (pin "K2") (pinfunction "PA3_K2") (pintype "input"))
    )
    (net (code "71") (name "unconnected-(U1-PA15-PadA8)") (class "Default")
      (node (ref "U1") (pin "A8") (pinfunction "PA15_A8") (pintype "input"))
    )
    (net (code "72") (name "unconnected-(U1-PB2-PadG5)") (class "Default")
      (node (ref "U1") (pin "G5") (pinfunction "PB2_G5") (pintype "input"))
    )
    (net (code "73") (name "unconnected-(U1-PB4-PadA6)") (class "Default")
      (node (ref "U1") (pin "A6") (pinfunction "PB4_A6") (pintype "input"))
    )
    (net (code "74") (name "unconnected-(U1-PB5-PadC5)") (class "Default")
      (node (ref "U1") (pin "C5") (pinfunction "PB5_C5") (pintype "input"))
    )
    (net (code "75") (name "unconnected-(U1-PB8-PadB4)") (class "Default")
      (node (ref "U1") (pin "B4") (pinfunction "PB8_B4") (pintype "input"))
    )
    (net (code "76") (name "unconnected-(U1-PB9-PadA4)") (class "Default")
      (node (ref "U1") (pin "A4") (pinfunction "PB9_A4") (pintype "input"))
    )
    (net (code "77") (name "unconnected-(U1-PC3_C-PadF3)") (class "Default")
      (node (ref "U1") (pin "F3") (pinfunction "PC3_C_F3") (pintype "input"))
    )
    (net (code "78") (name "unconnected-(U1-PC4-PadG4)") (class "Default")
      (node (ref "U1") (pin "G4") (pinfunction "PC4_G4") (pintype "input"))
    )
    (net (code "79") (name "unconnected-(U1-PC5-PadH4)") (class "Default")
      (node (ref "U1") (pin "H4") (pinfunction "PC5_H4") (pintype "input"))
    )
    (net (code "80") (name "unconnected-(U1-PC10-PadB9)") (class "Default")
      (node (ref "U1") (pin "B9") (pinfunction "PC10_B9") (pintype "input"))
    )
    (net (code "81") (name "unconnected-(U1-PC11-PadB8)") (class "Default")
      (node (ref "U1") (pin "B8") (pinfunction "PC11_B8") (pintype "input"))
    )
    (net (code "82") (name "unconnected-(U1-PC12-PadC8)") (class "Default")
      (node (ref "U1") (pin "C8") (pinfunction "PC12_C8") (pintype "input"))
    )
    (net (code "83") (name "unconnected-(U1-PC14-OSC32_IN-PadA1)") (class "Default")
      (node (ref "U1") (pin "A1") (pinfunction "PC14-OSC32_IN_A1") (pintype "input"))
    )
    (net (code "84") (name "unconnected-(U1-PC15-OSC32_OUT-PadB1)") (class "Default")
      (node (ref "U1") (pin "B1") (pinfunction "PC15-OSC32_OUT_B1") (pintype "input"))
    )
    (net (code "85") (name "unconnected-(U1-PD2-PadB7)") (class "Default")
      (node (ref "U1") (pin "B7") (pinfunction "PD2_B7") (pintype "input"))
    )
    (net (code "86") (name "unconnected-(U1-PD3-PadC7)") (class "Default")
      (node (ref "U1") (pin "C7") (pinfunction "PD3_C7") (pintype "input"))
    )
    (net (code "87") (name "unconnected-(U1-PD4-PadD7)") (class "Default")
      (node (ref "U1") (pin "D7") (pinfunction "PD4_D7") (pintype "input"))
    )
    (net (code "88") (name "unconnected-(U1-PD7-PadD6)") (class "Default")
      (node (ref "U1") (pin "D6") (pinfunction "PD7_D6") (pintype "input"))
    )
    (net (code "89") (name "unconnected-(U1-PD10-PadH9)") (class "Default")
      (node (ref "U1") (pin "H9") (pinfunction "PD10_H9") (pintype "input"))
    )
    (net (code "90") (name "unconnected-(U1-PD11-PadG9)") (class "Default")
      (node (ref "U1") (pin "G9") (pinfunction "PD11_G9") (pintype "input"))
    )
    (net (code "91") (name "unconnected-(U1-PD13-PadJ10)") (class "Default")
      (node (ref "U1") (pin "J10") (pinfunction "PD13_J10") (pintype "input"))
    )
    (net (code "92") (name "unconnected-(U1-PD14-PadH8)") (class "Default")
      (node (ref "U1") (pin "H8") (pinfunction "PD14_H8") (pintype "input"))
    )
    (net (code "93") (name "unconnected-(U1-PD15-PadG8)") (class "Default")
      (node (ref "U1") (pin "G8") (pinfunction "PD15_G8") (pintype "input"))
    )
    (net (code "94") (name "unconnected-(U1-PDR_ON-PadF7)") (class "Default")
      (node (ref "U1") (pin "F7") (pinfunction "PDR_ON_F7") (pintype "input"))
    )
    (net (code "95") (name "unconnected-(U1-PE0-PadD4)") (class "Default")
      (node (ref "U1") (pin "D4") (pinfunction "PE0_D4") (pintype "input"))
    )
    (net (code "96") (name "unconnected-(U1-PE1-PadC4)") (class "Default")
      (node (ref "U1") (pin "C4") (pinfunction "PE1_C4") (pintype "input"))
    )
    (net (code "97") (name "unconnected-(U1-PE3-PadB3)") (class "Default")
      (node (ref "U1") (pin "B3") (pinfunction "PE3_B3") (pintype "input"))
    )
    (net (code "98") (name "unconnected-(U1-PE9-PadK5)") (class "Default")
      (node (ref "U1") (pin "K5") (pinfunction "PE9_K5") (pintype "input"))
    )
    (net (code "99") (name "unconnected-(U1-PE10-PadG6)") (class "Default")
      (node (ref "U1") (pin "G6") (pinfunction "PE10_G6") (pintype "input"))
    )
    (net (code "100") (name "unconnected-(U1-PE11-PadH6)") (class "Default")
      (node (ref "U1") (pin "H6") (pinfunction "PE11_H6") (pintype "input"))
    )
    (net (code "101") (name "unconnected-(U1-PE12-PadJ6)") (class "Default")
      (node (ref "U1") (pin "J6") (pinfunction "PE12_J6") (pintype "input"))
    )
    (net (code "102") (name "unconnected-(U1-PE13-PadK6)") (class "Default")
      (node (ref "U1") (pin "K6") (pinfunction "PE13_K6") (pintype "input"))
    )
    (net (code "103") (name "unconnected-(U1-PE14-PadG7)") (class "Default")
      (node (ref "U1") (pin "G7") (pinfunction "PE14_G7") (pintype "input"))
    )
    (net (code "104") (name "unconnected-(U1-PE15-PadH7)") (class "Default")
      (node (ref "U1") (pin "H7") (pinfunction "PE15_H7") (pintype "input"))
    )
    (net (code "105") (name "unconnected-(U1-VBAT-PadB2)") (class "Default")
      (node (ref "U1") (pin "B2") (pinfunction "VBAT_B2") (pintype "input"))
    )
    (net (code "106") (name "unconnected-(U1-VCAP-PadE7)") (class "Default")
      (node (ref "U1") (pin "E7") (pinfunction "VCAP_E7") (pintype "input"))
    )
    (net (code "107") (name "unconnected-(U1-VCAP-PadF8)") (class "Default")
      (node (ref "U1") (pin "F8") (pinfunction "VCAP_F8") (pintype "input"))
    )
    (net (code "108") (name "unconnected-(U1-VDD-PadD2)") (class "Default")
      (node (ref "U1") (pin "D2") (pinfunction "VDD_D2") (pintype "input"))
    )
    (net (code "109") (name "unconnected-(U1-VDD-PadF5)") (class "Default")
      (node (ref "U1") (pin "F5") (pinfunction "VDD_F5") (pintype "input"))
    )
    (net (code "110") (name "unconnected-(U1-VDD-PadK1)") (class "Default")
      (node (ref "U1") (pin "K1") (pinfunction "VDD_K1") (pintype "input"))
    )
    (net (code "111") (name "unconnected-(U1-VDDA-PadH1)") (class "Default")
      (node (ref "U1") (pin "H1") (pinfunction "VDDA_H1") (pintype "input"))
    )
    (net (code "112") (name "unconnected-(U1-VDDLDO-PadF4)") (class "Default")
      (node (ref "U1") (pin "F4") (pinfunction "VDDLDO_F4") (pintype "input"))
    )
    (net (code "113") (name "unconnected-(U1-VSS-PadC2)") (class "Default")
      (node (ref "U1") (pin "C2") (pinfunction "VSS_C2") (pintype "input"))
    )
    (net (code "114") (name "unconnected-(U1-VSS-PadJ1)") (class "Default")
      (node (ref "U1") (pin "J1") (pinfunction "VSS_J1") (pintype "input"))
    )
    (net (code "115") (name "unconnected-(U1-VSSA-PadG1)") (class "Default")
      (node (ref "U1") (pin "G1") (pinfunction "VSSA_G1") (pintype "input"))
    )
    (net (code "116") (name "unconnected-(U3-CLKOUT-Pad7)") (class "Default")
      (node (ref "U3") (pin "7") (pinfunction "CLKOUT_7") (pintype "input+no_connect"))
    )
    (net (code "117") (name "unconnected-(U3-NC-Pad1)") (class "Default")
      (node (ref "U3") (pin "1") (pinfunction "NC_1") (pintype "input+no_connect"))
    )
    (net (code "118") (name "unconnected-(U3-NC-Pad2)") (class "Default")
      (node (ref "U3") (pin "2") (pinfunction "NC_2") (pintype "input+no_connect"))
    )
    (net (code "119") (name "unconnected-(U3-NC-Pad14)") (class "Default")
      (node (ref "U3") (pin "14") (pinfunction "NC_14") (pintype "input+no_connect"))
    )
    (net (code "120") (name "unconnected-(U3-NC-Pad15)") (class "Default")
      (node (ref "U3") (pin "15") (pinfunction "NC_15") (pintype "input+no_connect"))
    )
    (net (code "121") (name "unconnected-(U3-NC-Pad16)") (class "Default")
      (node (ref "U3") (pin "16") (pinfunction "NC_16") (pintype "input+no_connect"))
    )
    (net (code "122") (name "unconnected-(U3-NC-Pad27)") (class "Default")
      (node (ref "U3") (pin "27") (pinfunction "NC_27") (pintype "input+no_connect"))
    )
    (net (code "123") (name "unconnected-(U3-NC-Pad28)") (class "Default")
      (node (ref "U3") (pin "28") (pinfunction "NC_28") (pintype "input+no_connect"))
    )
    (net (code "124") (name "unconnected-(U3-SYNC_IN-Pad13)") (class "Default")
      (node (ref "U3") (pin "13") (pinfunction "SYNC_IN_13") (pintype "input+no_connect"))
    )
    (net (code "125") (name "unconnected-(U5-Pad1)") (class "Default")
      (node (ref "U5") (pin "1") (pinfunction "1_1") (pintype "input"))
    )
    (net (code "126") (name "unconnected-(U6-Pad1)") (class "Default")
      (node (ref "U6") (pin "1") (pinfunction "1_1") (pintype "input"))
    )
    (net (code "127") (name "unconnected-(U7-Pad1)") (class "Default")
      (node (ref "U7") (pin "1") (pinfunction "1_1") (pintype "input"))
    )
    (net (code "128") (name "unconnected-(U8-Pad1)") (class "Default")
      (node (ref "U8") (pin "1") (pinfunction "1_1") (pintype "input"))
    )
    (net (code "129") (name "unconnected-(U9-Pad1)") (class "Default")
      (node (ref "U9") (pin "1") (pinfunction "1_1") (pintype "input"))
    )
    (net (code "130") (name "unconnected-(U10-Pad1)") (class "Default")
      (node (ref "U10") (pin "1") (pinfunction "1_1") (pintype "input"))
    )
    (net (code "131") (name "unconnected-(U11-Pad1)") (class "Default")
      (node (ref "U11") (pin "1") (pinfunction "1_1") (pintype "input"))
    )
    (net (code "132") (name "unconnected-(U12-Pad1)") (class "Default")
      (node (ref "U12") (pin "1") (pinfunction "1_1") (pintype "input"))
    )
    (net (code "133") (name "unconnected-(USBC1-SBU1-PadA8)") (class "Default")
      (node (ref "USBC1") (pin "A8") (pinfunction "SBU1_A8") (pintype "input+no_connect"))
    )
    (net (code "134") (name "unconnected-(USBC1-SBU2-PadB8)") (class "Default")
      (node (ref "USBC1") (pin "B8") (pinfunction "SBU2_B8") (pintype "input+no_connect"))
    )
  )
)
